# EqualizerChannel.net
KiCad netlist of a schematic drawn in Altium Designer
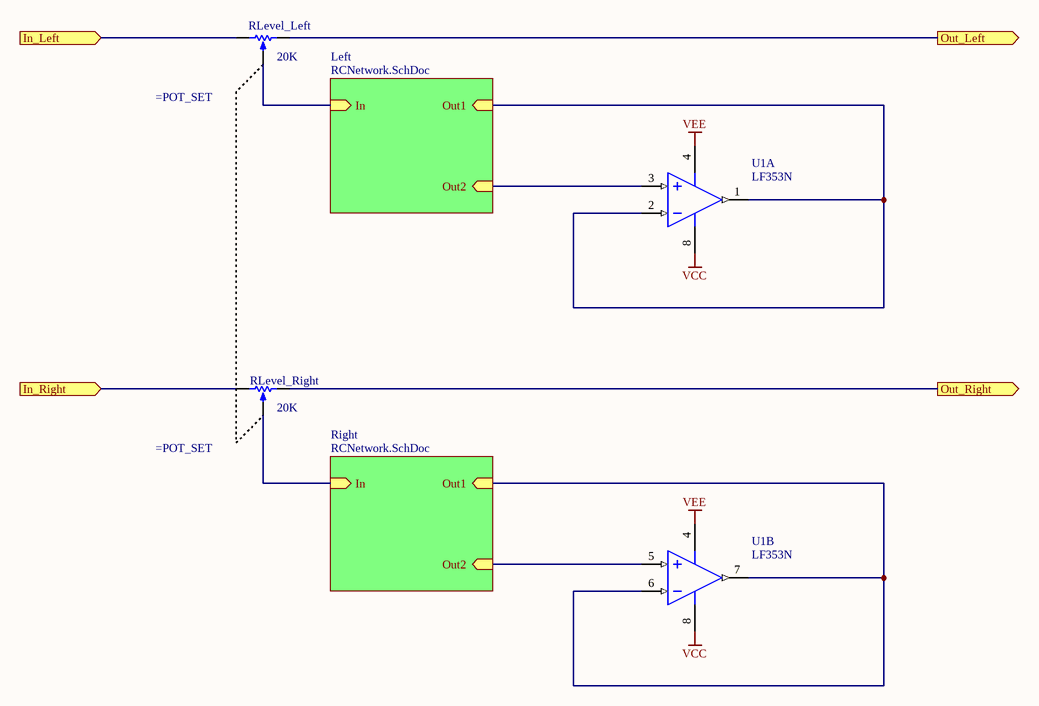
[diagram p0: EqualizerChannel.SchDoc]

(export (version "E")
  (design (tool "Eeschema 10.0.6"))
  (components
    (comp (ref "RLevel_Left")
      (value "20K")
      (footprint "AudioEqualizer:VR5")
      (description "Potentiometer")
      (fields (field (name "Comment") "RPot") (field (name "PUBLISHER") "Altium Limited"))
      (libsource (lib "Miscellaneous Devices") (part "RPot"))
    )
    (comp (ref "RLevel_Right")
      (value "20K")
      (footprint "AudioEqualizer:VR5")
      (description "Potentiometer")
      (fields (field (name "Comment") "RPot") (field (name "PUBLISHER") "Altium Limited"))
      (libsource (lib "Miscellaneous Devices") (part "RPot"))
    )
    (comp (ref "U1")
      (value "LF353N")
      (footprint "N08E")
      (description "Wide Bandwidth Dual JFET Input Operational Amplifier, 8-pin MDIP")
      (fields
        (field (name "MANUFACTURER") "National Semiconductor")
        (field (name "PUBLISHER") "Altium Limited")
      )
      (libsource (lib "NSC Amplifier") (part "LF353N"))
    )
  )
  (nets
    (net (code "1") (name "/In") (class "Default")
      (node (ref "RLevel_Left") (pin "3") (pinfunction "TAP_3") (pintype "passive"))
    )
    (net (code "2") (name "/In_1") (class "Default")
      (node (ref "RLevel_Right") (pin "3") (pinfunction "TAP_3") (pintype "passive"))
    )
    (net (code "3") (name "/In_Left") (class "Default")
      (node (ref "RLevel_Left") (pin "1") (pinfunction "TOP_1") (pintype "passive"))
    )
    (net (code "4") (name "/In_Right") (class "Default")
      (node (ref "RLevel_Right") (pin "1") (pinfunction "TOP_1") (pintype "passive"))
    )
    (net (code "5") (name "/Out1") (class "Default")
      (node (ref "U1") (pin "6") (pinfunction "INB-_6") (pintype "input"))
      (node (ref "U1") (pin "7") (pinfunction "OUTB_7") (pintype "output"))
    )
    (net (code "6") (name "/Out1_1") (class "Default")
      (node (ref "U1") (pin "1") (pinfunction "OUTA_1") (pintype "output"))
      (node (ref "U1") (pin "2") (pinfunction "INA-_2") (pintype "input"))
    )
    (net (code "7") (name "/Out2") (class "Default")
      (node (ref "U1") (pin "5") (pinfunction "INB+_5") (pintype "input"))
    )
    (net (code "8") (name "/Out2_1") (class "Default")
      (node (ref "U1") (pin "3") (pinfunction "INA+_3") (pintype "input"))
    )
    (net (code "9") (name "/Out_Left") (class "Default")
      (node (ref "RLevel_Left") (pin "2") (pinfunction "BOT_2") (pintype "passive"))
    )
    (net (code "10") (name "/Out_Right") (class "Default")
      (node (ref "RLevel_Right") (pin "2") (pinfunction "BOT_2") (pintype "passive"))
    )
    (net (code "11") (name "VCC") (class "Default")
      (node (ref "U1") (pin "8") (pinfunction "V+_8") (pintype "power_in"))
    )
    (net (code "12") (name "VEE") (class "Default")
      (node (ref "U1") (pin "4") (pinfunction "V-_4") (pintype "power_in"))
    )
  )
)
